# Trasnsmitter.net
KiCad netlist of a schematic drawn in EAGLE
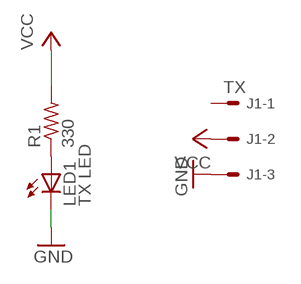
[diagram p0: schematic, sheet 1]

(export (version "E")
  (design (tool "Eeschema 10.0.6"))
  (components
    (comp (ref "J1")
      (value "TX")
      (footprint "eagle-import:7395-03")
      (libsource (lib "eagle-import") (part "CON_MOLEX-?-0305-7038"))
    )
    (comp (ref "LED1")
      (value "TX LED")
      (footprint "eagle-import:LED5MM")
      (libsource (lib "eagle-import") (part "LED5MM"))
    )
    (comp (ref "R1")
      (value "330")
      (footprint "eagle-import:0204_7")
      (libsource (lib "eagle-import") (part "RESISTOR0204/7"))
    )
  )
  (nets
    (net (code "1") (name "GND") (class "Default")
      (node (ref "J1") (pin "3") (pinfunction "S_3") (pintype "passive"))
      (node (ref "LED1") (pin "K") (pinfunction "C_K") (pintype "passive"))
    )
    (net (code "2") (name "Net-(LED1-PadA)") (class "Default")
      (node (ref "LED1") (pin "A") (pinfunction "A_A") (pintype "passive"))
      (node (ref "R1") (pin "1") (pinfunction "1_1") (pintype "passive"))
    )
    (net (code "3") (name "VCC") (class "Default")
      (node (ref "J1") (pin "2") (pinfunction "S_2") (pintype "passive"))
      (node (ref "R1") (pin "2") (pinfunction "2_2") (pintype "passive"))
    )
    (net (code "4") (name "unconnected-(J1A-S-Pad1)") (class "Default")
      (node (ref "J1") (pin "1") (pinfunction "S_1") (pintype "passive"))
    )
  )
)
